# 08_Power_Supply.net
KiCad netlist of a schematic drawn in Altium Designer
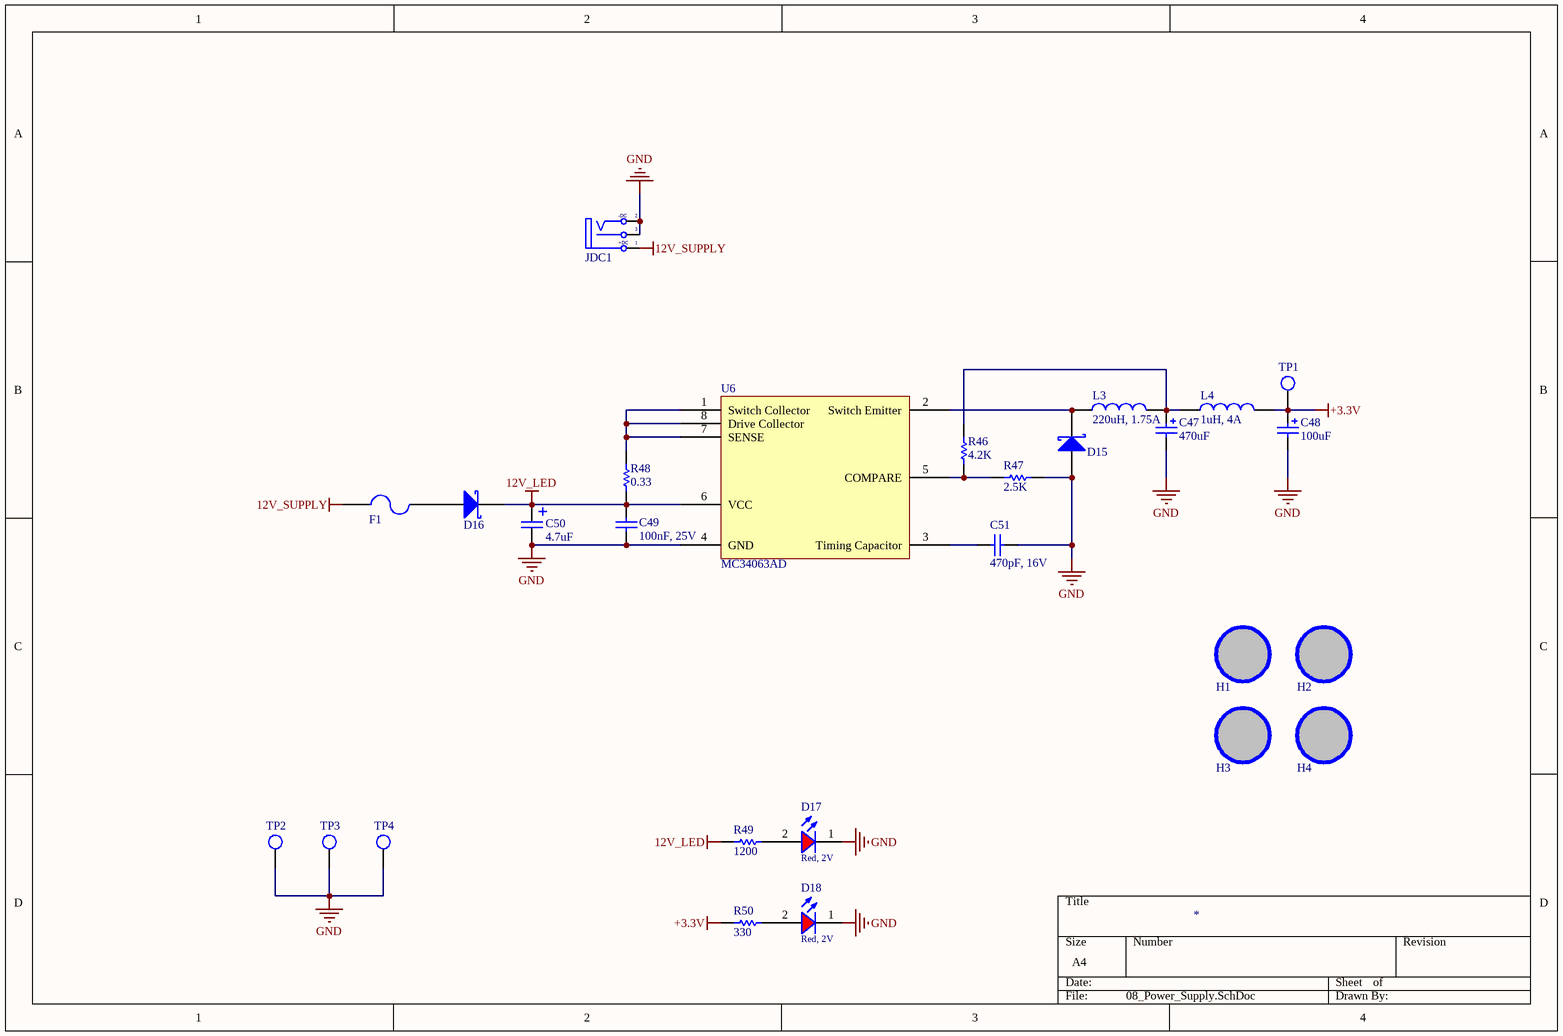
[diagram p0: 08_Power_Supply.SchDoc]

(export (version "E")
  (design (tool "Eeschema 10.0.6"))
  (components
    (comp (ref "C47")
      (value "470uF")
      (footprint "CAP ALU SIZE F")
      (description "Polarized Capacitor (Radial)")
      (fields (field (name "Comment") "Cap Pol SMD"))
      (libsource (lib "PIF_Library") (part "Cap Pol SMD"))
    )
    (comp (ref "C48")
      (value "100uF")
      (footprint "CAP ALU SIZE D")
      (description "Polarized Capacitor (Radial)")
      (fields (field (name "Comment") "Cap Pol SMD"))
      (libsource (lib "PIF_Library") (part "Cap Pol SMD"))
    )
    (comp (ref "C49")
      (value "100nF, 25V")
      (footprint "WCAP-CSGP_0603_H=0.8mm_Reflow")
      (description "WCAP-CSGP Multilayer Ceramic Chip Capacitor, General Purpose, size 0603, X7R, 100nF, 25V")
      (fields
        (field (name "MANUFACTURER PART NUMBER") "885012206071")
        (field (name "MANUFACTURER") "Wurth Elektronik")
      )
      (libsource (lib "Altium_WCAP-CSGP (rev20a)") (part "885012206071"))
    )
    (comp (ref "C50")
      (value "4.7uF")
      (footprint "CAPMP3216X18N")
      (fields (field (name "Comment") "Tantalum Capacitor"))
      (libsource (lib "MiclsLib") (part "Tantalum Capacitor"))
    )
    (comp (ref "C51")
      (value "470pF, 16V")
      (footprint "WCAP-CSGP_0603_H=0.8mm_Reflow")
      (description "WCAP-CSGP Multilayer Ceramic Chip Capacitor, General Purpose, size 0603, NP0, 470pF, 16V")
      (fields
        (field (name "MANUFACTURER PART NUMBER") "885012006027")
        (field (name "MANUFACTURER") "Wurth Elektronik")
      )
      (libsource (lib "Altium_WCAP-CSGP (rev20a)") (part "885012006027"))
    )
    (comp (ref "D15")
      (value "D Schottky")
      (footprint "SS34")
      (description "Schottky Diode")
      (fields (field (name "PUBLISHER") "Altium Limited"))
      (libsource (lib "PIF_Library") (part "D Schottky"))
    )
    (comp (ref "D16")
      (value "D Schottky")
      (footprint "SS34")
      (description "Schottky Diode")
      (fields (field (name "PUBLISHER") "Altium Limited"))
      (libsource (lib "PIF_Library") (part "D Schottky"))
    )
    (comp (ref "D17")
      (value "Red, 2V")
      (footprint "WL-SMCW_0603_H=0.7mm")
      (description "WL-SMCW SMT Mono-color Chip LED Waterclear, size 0603, Red, 2V, 140deg")
      (fields (field (name "PART NUMBER") "150060RS75000") (field (name "PUBLISHER") "Wurth Elektronik"))
      (libsource (lib "Altium_WL-SMCW (rev20a)") (part "150060RS75000"))
    )
    (comp (ref "D18")
      (value "Red, 2V")
      (footprint "WL-SMCW_0603_H=0.7mm")
      (description "WL-SMCW SMT Mono-color Chip LED Waterclear, size 0603, Red, 2V, 140deg")
      (fields (field (name "PART NUMBER") "150060RS75000") (field (name "PUBLISHER") "Wurth Elektronik"))
      (libsource (lib "Altium_WL-SMCW (rev20a)") (part "150060RS75000"))
    )
    (comp (ref "F1") (value "Fuse") (footprint "FUSE SMD") (libsource (lib "PIF_Library") (part "Fuse")))
    (comp (ref "H1")
      (value "Hole")
      (footprint "LO KHOAN 3MM")
      (description "Hole 3mm")
      (libsource (lib "PIF_Library") (part "Hole"))
    )
    (comp (ref "H2")
      (value "Hole")
      (footprint "LO KHOAN 3MM")
      (description "Hole 3mm")
      (libsource (lib "PIF_Library") (part "Hole"))
    )
    (comp (ref "H3")
      (value "Hole")
      (footprint "LO KHOAN 3MM")
      (description "Hole 3mm")
      (libsource (lib "PIF_Library") (part "Hole"))
    )
    (comp (ref "H4")
      (value "Hole")
      (footprint "LO KHOAN 3MM")
      (description "Hole 3mm")
      (libsource (lib "PIF_Library") (part "Hole"))
    )
    (comp (ref "JDC1")
      (value "Jack DC")
      (footprint "DC-IN")
      (description "Jack DC input")
      (libsource (lib "PIF_Library") (part "Jack DC"))
    )
    (comp (ref "L3")
      (value "220uH, 1.75A")
      (footprint "WE-PD2A_5848")
      (description "WE-PD2A SMT Power Inductor, size 5848, 220uH, 0.41A")
      (fields
        (field (name "MANUFACTURER PART NUMBER") "784774222")
        (field (name "MANUFACTURER") "Wurth Elektronik")
      )
      (libsource (lib "Altium_WE-PD2A (rev20a)") (part "784774222"))
    )
    (comp (ref "L4")
      (value "1uH, 4A")
      (footprint "WE-PD2A_4532")
      (description "WE-PD2A SMT Power Inductor, size 4532, 1uH, 4A")
      (fields
        (field (name "MANUFACTURER PART NUMBER") "7847730")
        (field (name "MANUFACTURER") "Wurth Elektronik")
      )
      (libsource (lib "Altium_WE-PD2A (rev20a)") (part "7847730"))
    )
    (comp (ref "R46")
      (value "4.2K")
      (footprint "RES-SM-0603")
      (description "Resistor")
      (fields (field (name "Comment") "RESISTOR SMD"))
      (libsource (lib "PIF_Library") (part "RESISTOR SMD"))
    )
    (comp (ref "R47")
      (value "2.5K")
      (footprint "RES-SM-0603")
      (description "Resistor")
      (fields (field (name "Comment") "RESISTOR SMD"))
      (libsource (lib "PIF_Library") (part "RESISTOR SMD"))
    )
    (comp (ref "R48")
      (value "0.33")
      (footprint "RES-SM-0805")
      (description "Resistor")
      (fields (field (name "Comment") "RESISTOR SMD"))
      (libsource (lib "PIF_Library") (part "RESISTOR SMD"))
    )
    (comp (ref "R49")
      (value "1200")
      (footprint "RES-SM-0603")
      (description "Resistor")
      (fields (field (name "Comment") "RESISTOR SMD"))
      (libsource (lib "PIF_Library") (part "RESISTOR SMD"))
    )
    (comp (ref "R50")
      (value "330")
      (footprint "RES-SM-0603")
      (description "Resistor")
      (fields (field (name "Comment") "RESISTOR SMD"))
      (libsource (lib "PIF_Library") (part "RESISTOR SMD"))
    )
    (comp (ref "TP1") (value "Test point") (footprint "TP") (libsource (lib "MiclsLib") (part "TP")))
    (comp (ref "TP2") (value "Test point") (footprint "TP") (libsource (lib "MiclsLib") (part "TP")))
    (comp (ref "TP3") (value "Test point") (footprint "TP") (libsource (lib "MiclsLib") (part "TP")))
    (comp (ref "TP4") (value "Test point") (footprint "TP") (libsource (lib "MiclsLib") (part "TP")))
    (comp (ref "U6")
      (value "MC34063AD")
      (footprint "SOIC127P600X170-8N")
      (description "1.5-A boost, buck, inverting switching regulator, operation from 0°C to 70°C")
      (fields (field (name "MANUFACTURER") "Texas Instruments"))
      (libsource (lib "PowerSupply") (part "MC34063"))
    )
  )
  (nets
    (net (code "1") (name "+3.3V") (class "Default")
      (node (ref "C48") (pin "1") (pinfunction "1_1") (pintype "passive"))
      (node (ref "L4") (pin "2") (pinfunction "2_2") (pintype "passive"))
      (node (ref "R50") (pin "2") (pinfunction "2_2") (pintype "passive"))
      (node (ref "TP1") (pin "1") (pinfunction "27_1") (pintype "passive"))
    )
    (net (code "2") (name "12V_LED") (class "Default")
      (node (ref "C49") (pin "2") (pinfunction "2_2") (pintype "passive"))
      (node (ref "C50") (pin "1") (pinfunction "1_1") (pintype "passive"))
      (node (ref "D16") (pin "2") (pinfunction "K_2") (pintype "passive"))
      (node (ref "R48") (pin "1") (pinfunction "1_1") (pintype "passive"))
      (node (ref "R49") (pin "2") (pinfunction "2_2") (pintype "passive"))
      (node (ref "U6") (pin "6") (pinfunction "VCC_6") (pintype "passive"))
    )
    (net (code "3") (name "12V_SUPPLY") (class "Default")
      (node (ref "F1") (pin "1") (pinfunction "1_1") (pintype "passive"))
      (node (ref "JDC1") (pin "1") (pinfunction "T_1") (pintype "passive"))
    )
    (net (code "4") (name "GND") (class "Default")
      (node (ref "C47") (pin "2") (pinfunction "2_2") (pintype "passive"))
      (node (ref "C48") (pin "2") (pinfunction "2_2") (pintype "passive"))
      (node (ref "C49") (pin "1") (pinfunction "1_1") (pintype "passive"))
      (node (ref "C50") (pin "2") (pinfunction "2_2") (pintype "passive"))
      (node (ref "C51") (pin "2") (pinfunction "2_2") (pintype "passive"))
      (node (ref "D15") (pin "1") (pinfunction "A_1") (pintype "passive"))
      (node (ref "D17") (pin "1") (pinfunction "K_1") (pintype "passive"))
      (node (ref "D18") (pin "1") (pinfunction "K_1") (pintype "passive"))
      (node (ref "JDC1") (pin "2") (pinfunction "TN_2") (pintype "passive"))
      (node (ref "JDC1") (pin "3") (pinfunction "S_3") (pintype "power_in"))
      (node (ref "R47") (pin "1") (pinfunction "1_1") (pintype "passive"))
      (node (ref "TP2") (pin "1") (pinfunction "27_1") (pintype "passive"))
      (node (ref "TP3") (pin "1") (pinfunction "27_1") (pintype "passive"))
      (node (ref "TP4") (pin "1") (pinfunction "27_1") (pintype "passive"))
      (node (ref "U6") (pin "4") (pinfunction "GND_4") (pintype "passive"))
    )
    (net (code "5") (name "Net-(C47-Pad1)") (class "Default")
      (node (ref "C47") (pin "1") (pinfunction "1_1") (pintype "passive"))
      (node (ref "L3") (pin "2") (pinfunction "2_2") (pintype "passive"))
      (node (ref "L4") (pin "1") (pinfunction "1_1") (pintype "passive"))
      (node (ref "R46") (pin "2") (pinfunction "2_2") (pintype "passive"))
    )
    (net (code "6") (name "Net-(D15-K)") (class "Default")
      (node (ref "D15") (pin "2") (pinfunction "K_2") (pintype "passive"))
      (node (ref "L3") (pin "1") (pinfunction "1_1") (pintype "passive"))
      (node (ref "U6") (pin "2") (pinfunction "Switch_Emitter_2") (pintype "passive"))
    )
    (net (code "7") (name "Net-(D16-A)") (class "Default")
      (node (ref "D16") (pin "1") (pinfunction "A_1") (pintype "passive"))
      (node (ref "F1") (pin "2") (pinfunction "2_2") (pintype "passive"))
    )
    (net (code "8") (name "Net-(D17-A)") (class "Default")
      (node (ref "D17") (pin "2") (pinfunction "A_2") (pintype "passive"))
      (node (ref "R49") (pin "1") (pinfunction "1_1") (pintype "passive"))
    )
    (net (code "9") (name "Net-(D18-A)") (class "Default")
      (node (ref "D18") (pin "2") (pinfunction "A_2") (pintype "passive"))
      (node (ref "R50") (pin "1") (pinfunction "1_1") (pintype "passive"))
    )
    (net (code "10") (name "Net-(U6-COMPARE)") (class "Default")
      (node (ref "R46") (pin "1") (pinfunction "1_1") (pintype "passive"))
      (node (ref "R47") (pin "2") (pinfunction "2_2") (pintype "passive"))
      (node (ref "U6") (pin "5") (pinfunction "COMPARE_5") (pintype "passive"))
    )
    (net (code "11") (name "Net-(U6-Drive_Collector)") (class "Default")
      (node (ref "R48") (pin "2") (pinfunction "2_2") (pintype "passive"))
      (node (ref "U6") (pin "1") (pinfunction "Switch_Collector_1") (pintype "passive"))
      (node (ref "U6") (pin "7") (pinfunction "SENSE_7") (pintype "passive"))
      (node (ref "U6") (pin "8") (pinfunction "Drive_Collector_8") (pintype "passive"))
    )
    (net (code "12") (name "Net-(U6-Timing_Capacitor)") (class "Default")
      (node (ref "C51") (pin "1") (pinfunction "1_1") (pintype "passive"))
      (node (ref "U6") (pin "3") (pinfunction "Timing_Capacitor_3") (pintype "passive"))
    )
    (net (code "13") (name "unconnected-(H1-Pad1)") (class "Default")
      (node (ref "H1") (pin "1") (pinfunction "1_1") (pintype "passive"))
    )
    (net (code "14") (name "unconnected-(H2-Pad1)") (class "Default")
      (node (ref "H2") (pin "1") (pinfunction "1_1") (pintype "passive"))
    )
    (net (code "15") (name "unconnected-(H3-Pad1)") (class "Default")
      (node (ref "H3") (pin "1") (pinfunction "1_1") (pintype "passive"))
    )
    (net (code "16") (name "unconnected-(H4-Pad1)") (class "Default")
      (node (ref "H4") (pin "1") (pinfunction "1_1") (pintype "passive"))
    )
  )
)
